# led_serial_strip_hor.net
KiCad netlist of a schematic drawn in EAGLE
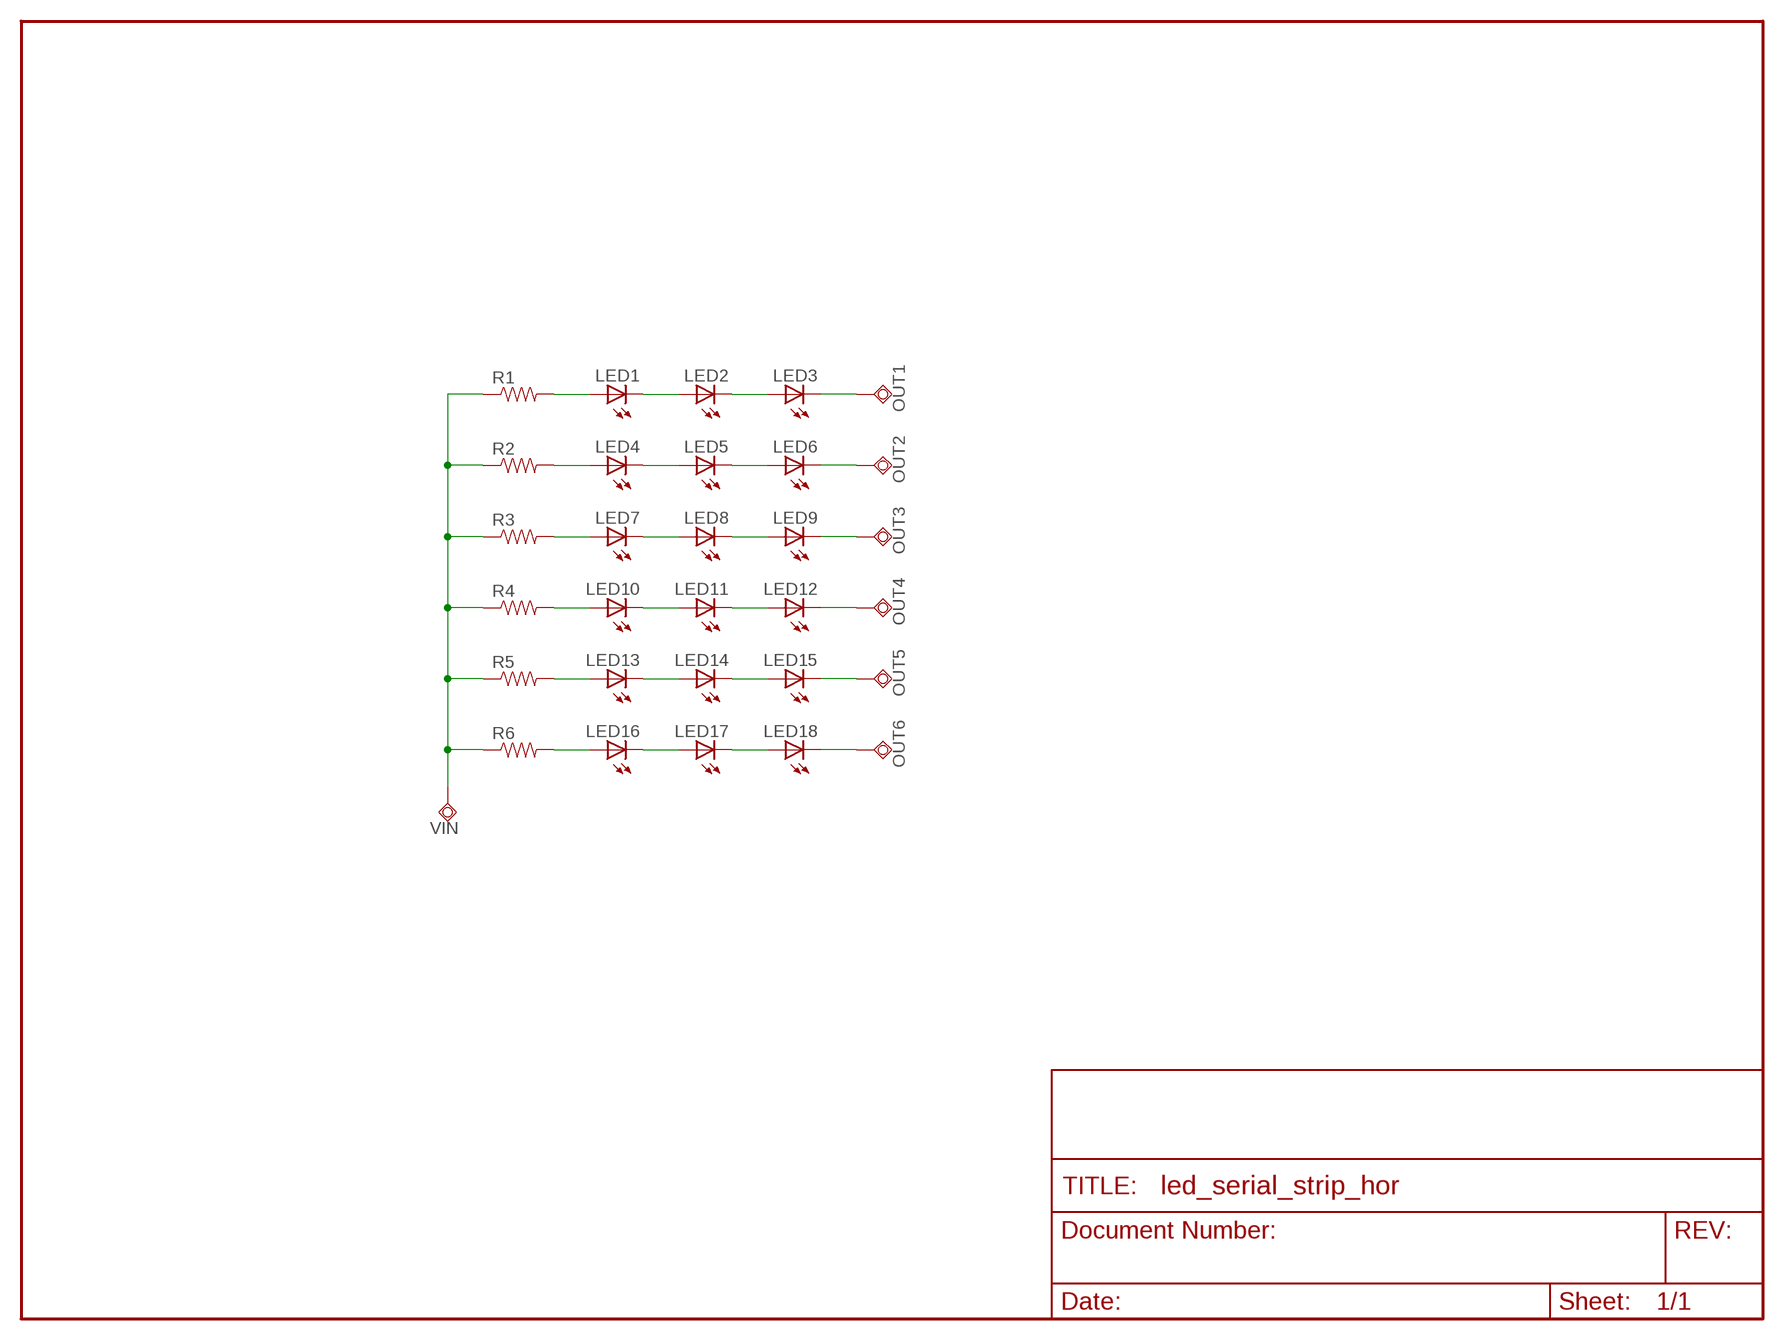
[diagram p0: schematic, sheet 1]

(export (version "E")
  (design (tool "Eeschema 10.0.6"))
  (components
    (comp (ref "LED1")
      (value "LED0805")
      (footprint "eagle-import:LED_0805")
      (libsource (lib "eagle-import") (part "LED0805"))
    )
    (comp (ref "LED2")
      (value "LED0805")
      (footprint "eagle-import:LED_0805")
      (libsource (lib "eagle-import") (part "LED0805"))
    )
    (comp (ref "LED3")
      (value "LED0805")
      (footprint "eagle-import:LED_0805")
      (libsource (lib "eagle-import") (part "LED0805"))
    )
    (comp (ref "LED4")
      (value "LED0805")
      (footprint "eagle-import:LED_0805")
      (libsource (lib "eagle-import") (part "LED0805"))
    )
    (comp (ref "LED5")
      (value "LED0805")
      (footprint "eagle-import:LED_0805")
      (libsource (lib "eagle-import") (part "LED0805"))
    )
    (comp (ref "LED6")
      (value "LED0805")
      (footprint "eagle-import:LED_0805")
      (libsource (lib "eagle-import") (part "LED0805"))
    )
    (comp (ref "LED7")
      (value "LED0805")
      (footprint "eagle-import:LED_0805")
      (libsource (lib "eagle-import") (part "LED0805"))
    )
    (comp (ref "LED8")
      (value "LED0805")
      (footprint "eagle-import:LED_0805")
      (libsource (lib "eagle-import") (part "LED0805"))
    )
    (comp (ref "LED9")
      (value "LED0805")
      (footprint "eagle-import:LED_0805")
      (libsource (lib "eagle-import") (part "LED0805"))
    )
    (comp (ref "LED10")
      (value "LED0805")
      (footprint "eagle-import:LED_0805")
      (libsource (lib "eagle-import") (part "LED0805"))
    )
    (comp (ref "LED11")
      (value "LED0805")
      (footprint "eagle-import:LED_0805")
      (libsource (lib "eagle-import") (part "LED0805"))
    )
    (comp (ref "LED12")
      (value "LED0805")
      (footprint "eagle-import:LED_0805")
      (libsource (lib "eagle-import") (part "LED0805"))
    )
    (comp (ref "LED13")
      (value "LED0805")
      (footprint "eagle-import:LED_0805")
      (libsource (lib "eagle-import") (part "LED0805"))
    )
    (comp (ref "LED14")
      (value "LED0805")
      (footprint "eagle-import:LED_0805")
      (libsource (lib "eagle-import") (part "LED0805"))
    )
    (comp (ref "LED15")
      (value "LED0805")
      (footprint "eagle-import:LED_0805")
      (libsource (lib "eagle-import") (part "LED0805"))
    )
    (comp (ref "LED16")
      (value "LED0805")
      (footprint "eagle-import:LED_0805")
      (libsource (lib "eagle-import") (part "LED0805"))
    )
    (comp (ref "LED17")
      (value "LED0805")
      (footprint "eagle-import:LED_0805")
      (libsource (lib "eagle-import") (part "LED0805"))
    )
    (comp (ref "LED18")
      (value "LED0805")
      (footprint "eagle-import:LED_0805")
      (libsource (lib "eagle-import") (part "LED0805"))
    )
    (comp (ref "OUT1")
      (value "TPSQTP15SQ")
      (footprint "eagle-import:TP15SQ")
      (libsource (lib "eagle-import") (part "TPSQTP15SQ"))
    )
    (comp (ref "OUT2")
      (value "TPSQTP15SQ")
      (footprint "eagle-import:TP15SQ")
      (libsource (lib "eagle-import") (part "TPSQTP15SQ"))
    )
    (comp (ref "OUT3")
      (value "TPSQTP15SQ")
      (footprint "eagle-import:TP15SQ")
      (libsource (lib "eagle-import") (part "TPSQTP15SQ"))
    )
    (comp (ref "OUT4")
      (value "TPSQTP15SQ")
      (footprint "eagle-import:TP15SQ")
      (libsource (lib "eagle-import") (part "TPSQTP15SQ"))
    )
    (comp (ref "OUT5")
      (value "TPSQTP15SQ")
      (footprint "eagle-import:TP15SQ")
      (libsource (lib "eagle-import") (part "TPSQTP15SQ"))
    )
    (comp (ref "OUT6")
      (value "TPSQTP15SQ")
      (footprint "eagle-import:TP15SQ")
      (libsource (lib "eagle-import") (part "TPSQTP15SQ"))
    )
    (comp (ref "R1")
      (value "RESISTOR0805-RES")
      (footprint "eagle-import:0805")
      (libsource (lib "eagle-import") (part "RESISTOR0805-RES"))
    )
    (comp (ref "R2")
      (value "RESISTOR0805-RES")
      (footprint "eagle-import:0805")
      (libsource (lib "eagle-import") (part "RESISTOR0805-RES"))
    )
    (comp (ref "R3")
      (value "RESISTOR0805-RES")
      (footprint "eagle-import:0805")
      (libsource (lib "eagle-import") (part "RESISTOR0805-RES"))
    )
    (comp (ref "R4")
      (value "RESISTOR0805-RES")
      (footprint "eagle-import:0805")
      (libsource (lib "eagle-import") (part "RESISTOR0805-RES"))
    )
    (comp (ref "R5")
      (value "RESISTOR0805-RES")
      (footprint "eagle-import:0805")
      (libsource (lib "eagle-import") (part "RESISTOR0805-RES"))
    )
    (comp (ref "R6")
      (value "RESISTOR0805-RES")
      (footprint "eagle-import:0805")
      (libsource (lib "eagle-import") (part "RESISTOR0805-RES"))
    )
    (comp (ref "VIN")
      (value "TPSQTP15SQ")
      (footprint "eagle-import:TP15SQ")
      (libsource (lib "eagle-import") (part "TPSQTP15SQ"))
    )
  )
  (nets
    (net (code "1") (name "Net-(LED1-PadA)") (class "Default")
      (node (ref "LED1") (pin "A") (pinfunction "A_A") (pintype "passive"))
      (node (ref "R1") (pin "2") (pinfunction "2_2") (pintype "passive"))
    )
    (net (code "2") (name "Net-(LED1-PadC)") (class "Default")
      (node (ref "LED1") (pin "C") (pinfunction "C_C") (pintype "passive"))
      (node (ref "LED2") (pin "A") (pinfunction "A_A") (pintype "passive"))
    )
    (net (code "3") (name "Net-(LED2-PadC)") (class "Default")
      (node (ref "LED2") (pin "C") (pinfunction "C_C") (pintype "passive"))
      (node (ref "LED3") (pin "A") (pinfunction "A_A") (pintype "passive"))
    )
    (net (code "4") (name "Net-(LED3-PadC)") (class "Default")
      (node (ref "LED3") (pin "C") (pinfunction "C_C") (pintype "passive"))
      (node (ref "OUT1") (pin "TP") (pinfunction "TP_TP") (pintype "input"))
    )
    (net (code "5") (name "Net-(LED4-PadA)") (class "Default")
      (node (ref "LED4") (pin "A") (pinfunction "A_A") (pintype "passive"))
      (node (ref "R2") (pin "2") (pinfunction "2_2") (pintype "passive"))
    )
    (net (code "6") (name "Net-(LED4-PadC)") (class "Default")
      (node (ref "LED4") (pin "C") (pinfunction "C_C") (pintype "passive"))
      (node (ref "LED5") (pin "A") (pinfunction "A_A") (pintype "passive"))
    )
    (net (code "7") (name "Net-(LED5-PadC)") (class "Default")
      (node (ref "LED5") (pin "C") (pinfunction "C_C") (pintype "passive"))
      (node (ref "LED6") (pin "A") (pinfunction "A_A") (pintype "passive"))
    )
    (net (code "8") (name "Net-(LED6-PadC)") (class "Default")
      (node (ref "LED6") (pin "C") (pinfunction "C_C") (pintype "passive"))
      (node (ref "OUT2") (pin "TP") (pinfunction "TP_TP") (pintype "input"))
    )
    (net (code "9") (name "Net-(LED7-PadA)") (class "Default")
      (node (ref "LED7") (pin "A") (pinfunction "A_A") (pintype "passive"))
      (node (ref "R3") (pin "2") (pinfunction "2_2") (pintype "passive"))
    )
    (net (code "10") (name "Net-(LED7-PadC)") (class "Default")
      (node (ref "LED7") (pin "C") (pinfunction "C_C") (pintype "passive"))
      (node (ref "LED8") (pin "A") (pinfunction "A_A") (pintype "passive"))
    )
    (net (code "11") (name "Net-(LED8-PadC)") (class "Default")
      (node (ref "LED8") (pin "C") (pinfunction "C_C") (pintype "passive"))
      (node (ref "LED9") (pin "A") (pinfunction "A_A") (pintype "passive"))
    )
    (net (code "12") (name "Net-(LED9-PadC)") (class "Default")
      (node (ref "LED9") (pin "C") (pinfunction "C_C") (pintype "passive"))
      (node (ref "OUT3") (pin "TP") (pinfunction "TP_TP") (pintype "input"))
    )
    (net (code "13") (name "Net-(LED10-PadA)") (class "Default")
      (node (ref "LED10") (pin "A") (pinfunction "A_A") (pintype "passive"))
      (node (ref "R4") (pin "2") (pinfunction "2_2") (pintype "passive"))
    )
    (net (code "14") (name "Net-(LED10-PadC)") (class "Default")
      (node (ref "LED10") (pin "C") (pinfunction "C_C") (pintype "passive"))
      (node (ref "LED11") (pin "A") (pinfunction "A_A") (pintype "passive"))
    )
    (net (code "15") (name "Net-(LED11-PadC)") (class "Default")
      (node (ref "LED11") (pin "C") (pinfunction "C_C") (pintype "passive"))
      (node (ref "LED12") (pin "A") (pinfunction "A_A") (pintype "passive"))
    )
    (net (code "16") (name "Net-(LED12-PadC)") (class "Default")
      (node (ref "LED12") (pin "C") (pinfunction "C_C") (pintype "passive"))
      (node (ref "OUT4") (pin "TP") (pinfunction "TP_TP") (pintype "input"))
    )
    (net (code "17") (name "Net-(LED13-PadA)") (class "Default")
      (node (ref "LED13") (pin "A") (pinfunction "A_A") (pintype "passive"))
      (node (ref "R5") (pin "2") (pinfunction "2_2") (pintype "passive"))
    )
    (net (code "18") (name "Net-(LED13-PadC)") (class "Default")
      (node (ref "LED13") (pin "C") (pinfunction "C_C") (pintype "passive"))
      (node (ref "LED14") (pin "A") (pinfunction "A_A") (pintype "passive"))
    )
    (net (code "19") (name "Net-(LED14-PadC)") (class "Default")
      (node (ref "LED14") (pin "C") (pinfunction "C_C") (pintype "passive"))
      (node (ref "LED15") (pin "A") (pinfunction "A_A") (pintype "passive"))
    )
    (net (code "20") (name "Net-(LED15-PadC)") (class "Default")
      (node (ref "LED15") (pin "C") (pinfunction "C_C") (pintype "passive"))
      (node (ref "OUT5") (pin "TP") (pinfunction "TP_TP") (pintype "input"))
    )
    (net (code "21") (name "Net-(LED16-PadA)") (class "Default")
      (node (ref "LED16") (pin "A") (pinfunction "A_A") (pintype "passive"))
      (node (ref "R6") (pin "2") (pinfunction "2_2") (pintype "passive"))
    )
    (net (code "22") (name "Net-(LED16-PadC)") (class "Default")
      (node (ref "LED16") (pin "C") (pinfunction "C_C") (pintype "passive"))
      (node (ref "LED17") (pin "A") (pinfunction "A_A") (pintype "passive"))
    )
    (net (code "23") (name "Net-(LED17-PadC)") (class "Default")
      (node (ref "LED17") (pin "C") (pinfunction "C_C") (pintype "passive"))
      (node (ref "LED18") (pin "A") (pinfunction "A_A") (pintype "passive"))
    )
    (net (code "24") (name "Net-(LED18-PadC)") (class "Default")
      (node (ref "LED18") (pin "C") (pinfunction "C_C") (pintype "passive"))
      (node (ref "OUT6") (pin "TP") (pinfunction "TP_TP") (pintype "input"))
    )
    (net (code "25") (name "Net-(R1-Pad1)") (class "Default")
      (node (ref "R1") (pin "1") (pinfunction "1_1") (pintype "passive"))
      (node (ref "R2") (pin "1") (pinfunction "1_1") (pintype "passive"))
      (node (ref "R3") (pin "1") (pinfunction "1_1") (pintype "passive"))
      (node (ref "R4") (pin "1") (pinfunction "1_1") (pintype "passive"))
      (node (ref "R5") (pin "1") (pinfunction "1_1") (pintype "passive"))
      (node (ref "R6") (pin "1") (pinfunction "1_1") (pintype "passive"))
      (node (ref "VIN") (pin "TP") (pinfunction "TP_TP") (pintype "input"))
    )
  )
)
